# Sheet1.net
KiCad netlist of a schematic drawn in Altium Designer
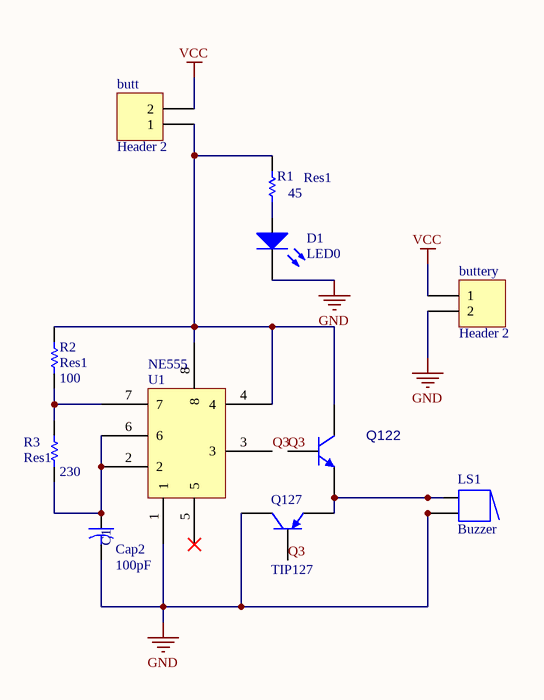
[diagram p0: Sheet1.SchDoc]

(export (version "E")
  (design (tool "Eeschema 10.0.6"))
  (components
    (comp (ref "butt")
      (value "Header 2")
      (footprint "HDR1X2")
      (description "Header, 2-Pin")
      (fields (field (name "PUBLISHER") "Altium Limited"))
      (libsource (lib "") (part "Header 2_1"))
    )
    (comp (ref "buttery")
      (value "Header 2")
      (footprint "HDR1X2")
      (description "Header, 2-Pin")
      (fields (field (name "PUBLISHER") "Altium Limited"))
      (libsource (lib "Miscellaneous Connectors") (part "Header 2"))
    )
    (comp (ref "C1")
      (value "Cap2")
      (footprint "CAPR5-4X5")
      (description "Capacitor")
      (fields (field (name "ALTIUM_VALUE") "100pF") (field (name "PUBLISHER") "Altium Limited"))
      (libsource (lib "Miscellaneous Devices") (part "Cap2"))
    )
    (comp (ref "D1")
      (value "LED0")
      (footprint "LED-0")
      (description "Typical INFRARED GaAs LED")
      (fields (field (name "PUBLISHER") "Altium Limited"))
      (libsource (lib "Miscellaneous Devices") (part "LED0"))
    )
    (comp (ref "LS1")
      (value "Buzzer")
      (footprint "ABSM-1574")
      (description "Magnetic Transducer Buzzer")
      (fields (field (name "PUBLISHER") "Altium Limited"))
      (libsource (lib "Miscellaneous Devices") (part "Buzzer"))
    )
    (comp (ref "Q122") (value "TIP122") (footprint "TIP122") (libsource (lib "TIP122") (part "TIP122")))
    (comp (ref "Q127")
      (value "TIP127")
      (footprint "TIP127")
      (fields (field (name "MF") "ON Semiconductor"))
      (libsource (lib "TIP127") (part "TIP127"))
    )
    (comp (ref "R1")
      (value "Res1")
      (footprint "AXIAL-0.3")
      (description "Resistor")
      (fields (field (name "ALTIUM_VALUE") "45") (field (name "PUBLISHER") "Altium Limited"))
      (libsource (lib "Miscellaneous Devices") (part "Res1"))
    )
    (comp (ref "R2")
      (value "Res1")
      (footprint "AXIAL-0.3")
      (description "Resistor")
      (fields (field (name "ALTIUM_VALUE") "100") (field (name "PUBLISHER") "Altium Limited"))
      (libsource (lib "Miscellaneous Devices") (part "Res1"))
    )
    (comp (ref "R3")
      (value "Res1")
      (footprint "AXIAL-0.3")
      (description "Resistor")
      (fields (field (name "ALTIUM_VALUE") "230") (field (name "PUBLISHER") "Altium Limited"))
      (libsource (lib "Miscellaneous Devices") (part "Res1"))
    )
    (comp (ref "U1") (value "NE555") (footprint "555") (libsource (lib "555") (part "555")))
  )
  (nets
    (net (code "1") (name "/Q3") (class "Default")
      (node (ref "Q122") (pin "1") (pinfunction "B_1") (pintype "passive"))
      (node (ref "Q127") (pin "1") (pinfunction "B_1") (pintype "passive"))
      (node (ref "U1") (pin "3") (pinfunction "3_3") (pintype "passive"))
    )
    (net (code "2") (name "GND") (class "Default")
      (node (ref "C1") (pin "2") (pinfunction "2_2") (pintype "passive"))
      (node (ref "D1") (pin "2") (pinfunction "K_2") (pintype "passive"))
      (node (ref "LS1") (pin "2") (pinfunction "2_2") (pintype "passive"))
      (node (ref "LS1") (pin "2A") (pinfunction "2A_2A") (pintype "passive"))
      (node (ref "Q127") (pin "2") (pinfunction "C_2") (pintype "passive"))
      (node (ref "U1") (pin "1") (pinfunction "1_1") (pintype "passive"))
      (node (ref "buttery") (pin "2") (pinfunction "2_2") (pintype "passive"))
    )
    (net (code "3") (name "Net-(C1-Pad1)") (class "Default")
      (node (ref "C1") (pin "1") (pinfunction "1_1") (pintype "passive"))
      (node (ref "R3") (pin "2") (pinfunction "2_2") (pintype "passive"))
      (node (ref "U1") (pin "2") (pinfunction "2_2") (pintype "passive"))
      (node (ref "U1") (pin "6") (pinfunction "6_6") (pintype "passive"))
    )
    (net (code "4") (name "Net-(D1-A)") (class "Default")
      (node (ref "D1") (pin "1") (pinfunction "A_1") (pintype "passive"))
      (node (ref "R1") (pin "1") (pinfunction "1_1") (pintype "passive"))
    )
    (net (code "5") (name "Net-(Q122-C)") (class "Default")
      (node (ref "Q122") (pin "2") (pinfunction "C_2") (pintype "passive"))
      (node (ref "R1") (pin "2") (pinfunction "2_2") (pintype "passive"))
      (node (ref "R2") (pin "1") (pinfunction "1_1") (pintype "passive"))
      (node (ref "U1") (pin "4") (pinfunction "4_4") (pintype "passive"))
      (node (ref "U1") (pin "8") (pinfunction "8_8") (pintype "passive"))
      (node (ref "butt") (pin "1") (pinfunction "1_1") (pintype "passive"))
    )
    (net (code "6") (name "Net-(Q122-E)") (class "Default")
      (node (ref "LS1") (pin "1") (pinfunction "1_1") (pintype "passive"))
      (node (ref "LS1") (pin "1A") (pinfunction "1A_1A") (pintype "passive"))
      (node (ref "Q122") (pin "3") (pinfunction "E_3") (pintype "passive"))
      (node (ref "Q127") (pin "3") (pinfunction "E_3") (pintype "passive"))
    )
    (net (code "7") (name "Net-(R2-Pad2)") (class "Default")
      (node (ref "R2") (pin "2") (pinfunction "2_2") (pintype "passive"))
      (node (ref "R3") (pin "1") (pinfunction "1_1") (pintype "passive"))
      (node (ref "U1") (pin "7") (pinfunction "7_7") (pintype "passive"))
    )
    (net (code "8") (name "VCC") (class "Default")
      (node (ref "butt") (pin "2") (pinfunction "2_2") (pintype "passive"))
      (node (ref "buttery") (pin "1") (pinfunction "1_1") (pintype "passive"))
    )
    (net (code "9") (name "unconnected-(U1-Pad5)") (class "Default")
      (node (ref "U1") (pin "5") (pinfunction "5_5") (pintype "passive+no_connect"))
    )
  )
)
